# AFE_isoSPI_Interface.net
KiCad netlist of a schematic drawn in Altium Designer
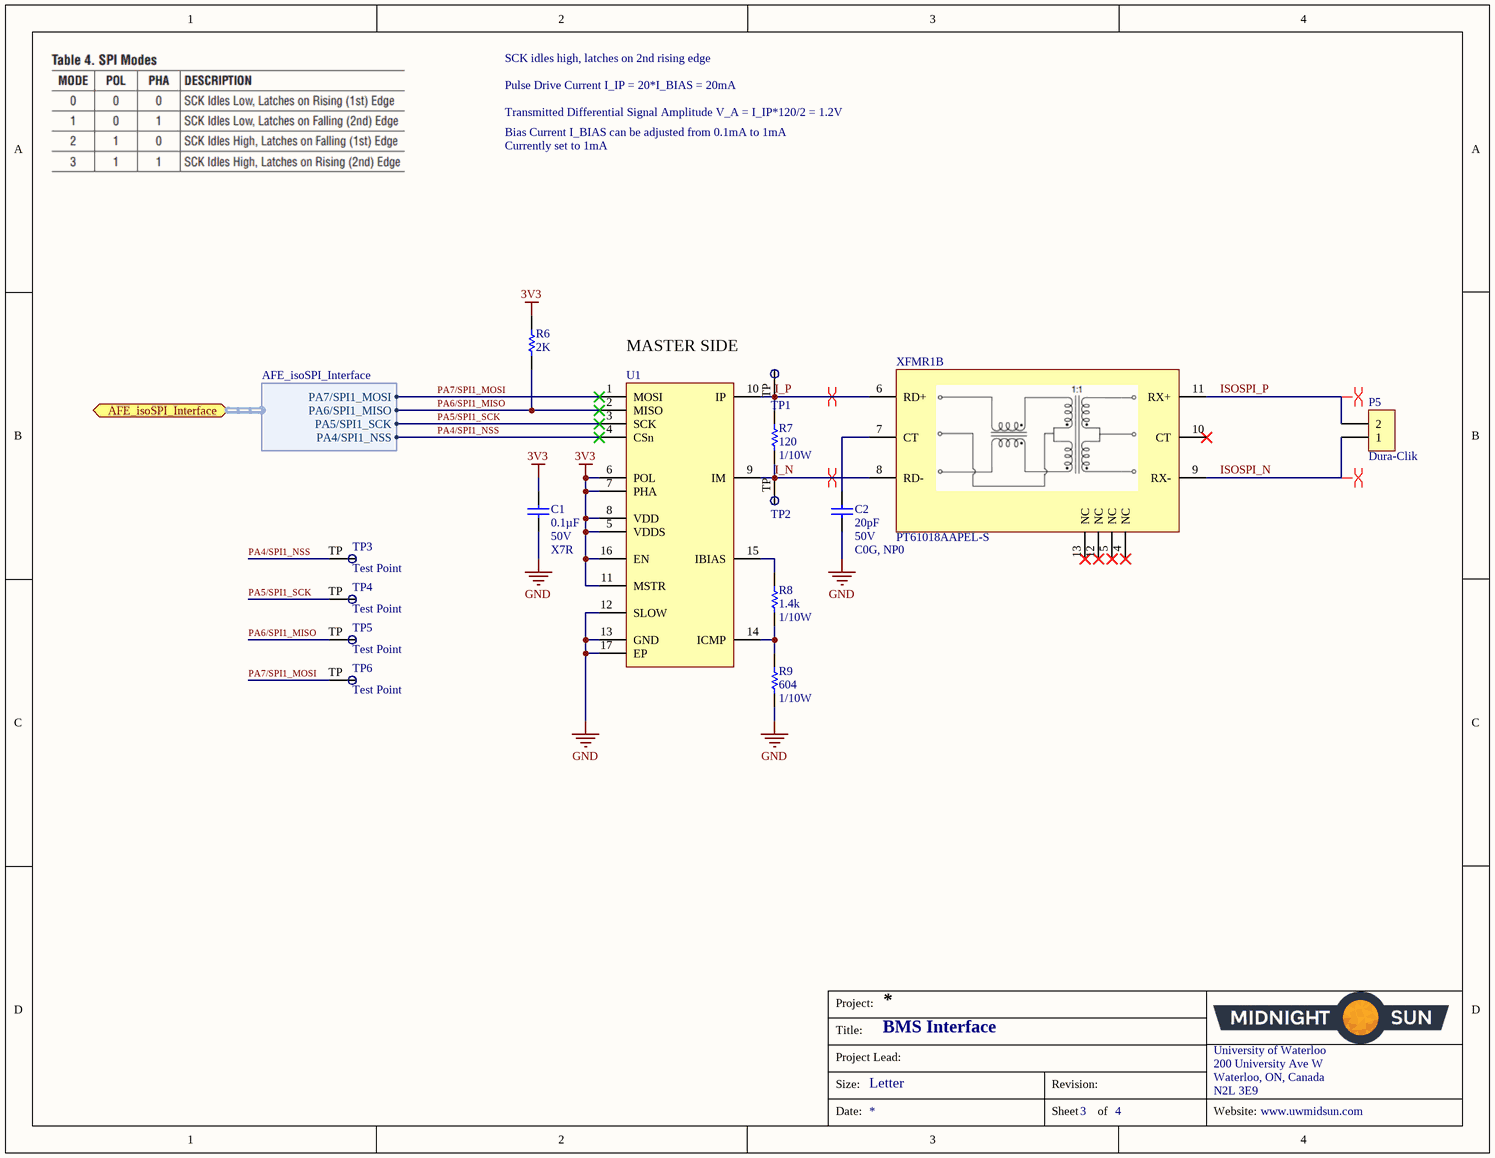
[diagram p0: AFE_isoSPI_Interface.SchDoc]

(export (version "E")
  (design (tool "Eeschema 10.0.6"))
  (components
    (comp (ref "C1")
      (value "CAP CER 0.1UF 50V 10% X7R 0603")
      (footprint "CAP, 0603")
      (description "0.10µF ±10% 50V Ceramic Capacitor X7R 0603 (1608 Metric)")
      (fields
        (field (name "TOLERANCE") "±10%")
        (field (name "CAPACITANCE") "0.1µF")
        (field (name "VOLTAGE") "50V")
        (field (name "TEMPERATURE COEFFICIENT") "X7R")
      )
      (libsource (lib "Schematic Diagrams") (part "CAP CER 0.1UF 50V 10% X7R 0603"))
    )
    (comp (ref "C2")
      (value "CAP CER 20PF 50V ±5% C0G/NP0 0603")
      (footprint "CAP, 0603")
      (description "20pF ±5% 50V Ceramic Capacitor C0G, NP0 0603 (1608 Metric)")
      (fields
        (field (name "TOLERANCE") "±5%")
        (field (name "CAPACITANCE") "20pF")
        (field (name "VOLTAGE") "50V")
        (field (name "TEMPERATURE COEFFICIENT") "C0G, NP0")
      )
      (libsource (lib "Schematic Diagrams") (part "CAP CER 20PF 50V ±5% C0G/NP0 0603"))
    )
    (comp (ref "P5")
      (value "Dura-Clik")
      (footprint "CONN, 2POS Dura-Click Vertical")
      (description "2 Positions Header, Shrouded Connector 0.079\" (2.00mm) Surface Mount, Vertical Tin")
      (fields
        (field (name "MANUFACTURER") "Molex, LLC")
        (field (name "MANUFACTURER PART NUMBER") "5600200220")
      )
      (libsource (lib "Schematic Diagrams") (part "CONN 2POS DURA-CLIK 0.079{dblquote} VERT"))
    )
    (comp (ref "R6")
      (value "2K")
      (footprint "RES, 0603")
      (description "2k Ohm ±1% 0.1W, 1/10W Chip Resistor 0603 (1608 Metric) Moisture Resistant Thick Film")
      (fields
        (field (name "MANUFACTURER") "Yageo")
        (field (name "MANUFACTURER PART NUMBER") "RC0603FR-072KL")
      )
      (libsource (lib "Schematic Diagrams") (part "RES 2K OHM 1% 1/10W 0603"))
    )
    (comp (ref "R7")
      (value "RES 120 OHM 1% 1/10W 0603")
      (footprint "RES, 0603")
      (description "RES SMD 120 OHM 1% 1/10W 0603")
      (fields
        (field (name "TOLERANCE") "±1%")
        (field (name "RESISTANCE") "120")
        (field (name "POWER") "1/10W")
      )
      (libsource (lib "Schematic Diagrams") (part "RES 120 OHM 1% 1/10W 0603"))
    )
    (comp (ref "R8")
      (value "RES 1.4k OHM 1% 1/10W 0603")
      (footprint "RES, 0603")
      (description "RES SMD 1.4K OHM 1% 1/10W 0603")
      (fields
        (field (name "TOLERANCE") "±1%")
        (field (name "RESISTANCE") "1.4k")
        (field (name "POWER") "1/10W")
      )
      (libsource (lib "Schematic Diagrams") (part "RES 1.4k OHM 1% 1/10W 0603"))
    )
    (comp (ref "R9")
      (value "RES 604 OHM 1% 1/10W 0603")
      (footprint "RES, 0603")
      (description "RES SMD 604 OHM 1% 1/10W 0603")
      (fields
        (field (name "TOLERANCE") "±1%")
        (field (name "RESISTANCE") "604")
        (field (name "POWER") "1/10W")
      )
      (libsource (lib "Schematic Diagrams") (part "RES 604 OHM 1% 1/10W 0603"))
    )
    (comp (ref "TP1")
      (value "Test Point")
      (footprint "Test Point")
      (libsource (lib "Schematic Diagrams") (part "Test Point"))
    )
    (comp (ref "TP2")
      (value "Test Point")
      (footprint "Test Point")
      (libsource (lib "Schematic Diagrams") (part "Test Point"))
    )
    (comp (ref "TP3")
      (value "Test Point")
      (footprint "Test Point")
      (libsource (lib "Schematic Diagrams") (part "Test Point"))
    )
    (comp (ref "TP4")
      (value "Test Point")
      (footprint "Test Point")
      (libsource (lib "Schematic Diagrams") (part "Test Point"))
    )
    (comp (ref "TP5")
      (value "Test Point")
      (footprint "Test Point")
      (libsource (lib "Schematic Diagrams") (part "Test Point"))
    )
    (comp (ref "TP6")
      (value "Test Point")
      (footprint "Test Point")
      (libsource (lib "Schematic Diagrams") (part "Test Point"))
    )
    (comp (ref "U1")
      (value "IC ISOSPI COMM INTERFACE LTC6820IUD")
      (footprint "IC COMM INTERFACE ISOSPI 16-QFN")
      (description "IC COMM INTERFACE ISOSPI 16-QFN")
      (fields
        (field (name "MANUFACTURER") "Linear Technology")
        (field (name "MANUFACTURER PART NUMBER") "LTC6820IUD#PBF")
      )
      (libsource (lib "Schematic Diagrams") (part "IC ISOSPI COMM INTERFACE LTC6820IUD"))
    )
    (comp (ref "XFMR1")
      (value "IC PULSE XFMR 1CT:1CT 350UH SMD")
      (footprint "IC, PULSE XFMR 1CT:1CT 350UH SMD")
      (description "PULSE XFMR 1CT:1CT 350UH SMD")
      (fields (field (name "MANUFACTURER") "Bourns Inc.") (field (name "MFG_PN") "PT61018AAPEL-S"))
      (libsource (lib "Schematic Diagrams") (part "IC PULSE XFMR 1CT{colon}1CT 350UH SMD"))
    )
  )
  (nets
    (net (code "2") (name "/ISOSPI_N") (class "Default")
      (node (ref "P5") (pin "1") (pinfunction "1_1") (pintype "passive"))
      (node (ref "XFMR1") (pin "9") (pinfunction "RX-_9") (pintype "passive"))
    )
    (net (code "3") (name "/ISOSPI_P") (class "Default")
      (node (ref "P5") (pin "2") (pinfunction "2_2") (pintype "passive"))
      (node (ref "XFMR1") (pin "11") (pinfunction "RX+_11") (pintype "passive"))
    )
    (net (code "4") (name "/I_N") (class "Default")
      (node (ref "R7") (pin "2") (pinfunction "2_2") (pintype "passive"))
      (node (ref "TP2") (pin "TP") (pinfunction "1_TP") (pintype "passive"))
      (node (ref "U1") (pin "9") (pinfunction "IM_9") (pintype "passive"))
      (node (ref "XFMR1") (pin "8") (pinfunction "RD-_8") (pintype "passive"))
    )
    (net (code "5") (name "/I_P") (class "Default")
      (node (ref "R7") (pin "1") (pinfunction "1_1") (pintype "passive"))
      (node (ref "TP1") (pin "TP") (pinfunction "1_TP") (pintype "passive"))
      (node (ref "U1") (pin "10") (pinfunction "IP_10") (pintype "passive"))
      (node (ref "XFMR1") (pin "6") (pinfunction "RD+_6") (pintype "passive"))
    )
    (net (code "6") (name "/PA4{slash}SPI1_NSS") (class "Default")
      (node (ref "TP3") (pin "TP") (pinfunction "1_TP") (pintype "passive"))
      (node (ref "U1") (pin "4") (pinfunction "CSn_4") (pintype "passive"))
    )
    (net (code "7") (name "/PA5{slash}SPI1_SCK") (class "Default")
      (node (ref "TP4") (pin "TP") (pinfunction "1_TP") (pintype "passive"))
      (node (ref "U1") (pin "3") (pinfunction "SCK_3") (pintype "passive"))
    )
    (net (code "8") (name "/PA6{slash}SPI1_MISO") (class "Default")
      (node (ref "R6") (pin "2") (pinfunction "2_2") (pintype "passive"))
      (node (ref "TP5") (pin "TP") (pinfunction "1_TP") (pintype "passive"))
      (node (ref "U1") (pin "2") (pinfunction "MISO_2") (pintype "passive"))
    )
    (net (code "9") (name "/PA7{slash}SPI1_MOSI") (class "Default")
      (node (ref "TP6") (pin "TP") (pinfunction "1_TP") (pintype "passive"))
      (node (ref "U1") (pin "1") (pinfunction "MOSI_1") (pintype "passive"))
    )
    (net (code "11") (name "3V3") (class "Default")
      (node (ref "C1") (pin "1") (pinfunction "1_1") (pintype "passive"))
      (node (ref "R6") (pin "1") (pinfunction "1_1") (pintype "passive"))
      (node (ref "U1") (pin "11") (pinfunction "MSTR_11") (pintype "passive"))
      (node (ref "U1") (pin "16") (pinfunction "EN_16") (pintype "passive"))
      (node (ref "U1") (pin "5") (pinfunction "VDDS_5") (pintype "passive"))
      (node (ref "U1") (pin "6") (pinfunction "POL_6") (pintype "passive"))
      (node (ref "U1") (pin "7") (pinfunction "PHA_7") (pintype "passive"))
      (node (ref "U1") (pin "8") (pinfunction "VDD_8") (pintype "passive"))
    )
    (net (code "12") (name "GND") (class "Default")
      (node (ref "C1") (pin "2") (pinfunction "2_2") (pintype "passive"))
      (node (ref "C2") (pin "2") (pinfunction "2_2") (pintype "passive"))
      (node (ref "R9") (pin "2") (pinfunction "2_2") (pintype "passive"))
      (node (ref "U1") (pin "12") (pinfunction "SLOW_12") (pintype "passive"))
      (node (ref "U1") (pin "13") (pinfunction "GND_13") (pintype "passive"))
      (node (ref "U1") (pin "17") (pinfunction "EP_17") (pintype "passive"))
    )
    (net (code "13") (name "Net-(C2-Pad1)") (class "Default")
      (node (ref "C2") (pin "1") (pinfunction "1_1") (pintype "passive"))
      (node (ref "XFMR1") (pin "7") (pinfunction "CT_7") (pintype "passive"))
    )
    (net (code "14") (name "Net-(U1-IBIAS)") (class "Default")
      (node (ref "R8") (pin "1") (pinfunction "1_1") (pintype "passive"))
      (node (ref "U1") (pin "15") (pinfunction "IBIAS_15") (pintype "passive"))
    )
    (net (code "15") (name "Net-(U1-ICMP)") (class "Default")
      (node (ref "R8") (pin "2") (pinfunction "2_2") (pintype "passive"))
      (node (ref "R9") (pin "1") (pinfunction "1_1") (pintype "passive"))
      (node (ref "U1") (pin "14") (pinfunction "ICMP_14") (pintype "passive"))
    )
    (net (code "16") (name "unconnected-(XFMR1B-CT-Pad10)") (class "Default")
      (node (ref "XFMR1") (pin "10") (pinfunction "CT_10") (pintype "passive+no_connect"))
    )
    (net (code "17") (name "unconnected-(XFMR1B-NC-Pad4)") (class "Default")
      (node (ref "XFMR1") (pin "4") (pinfunction "NC_4") (pintype "passive+no_connect"))
    )
    (net (code "18") (name "unconnected-(XFMR1B-NC-Pad5)") (class "Default")
      (node (ref "XFMR1") (pin "5") (pinfunction "NC_5") (pintype "passive+no_connect"))
    )
    (net (code "19") (name "unconnected-(XFMR1B-NC-Pad12)") (class "Default")
      (node (ref "XFMR1") (pin "12") (pinfunction "NC_12") (pintype "passive+no_connect"))
    )
    (net (code "20") (name "unconnected-(XFMR1B-NC-Pad13)") (class "Default")
      (node (ref "XFMR1") (pin "13") (pinfunction "NC_13") (pintype "passive+no_connect"))
    )
  )
)
